# 02_-_Sensor.net
KiCad netlist of a schematic drawn in Altium Designer
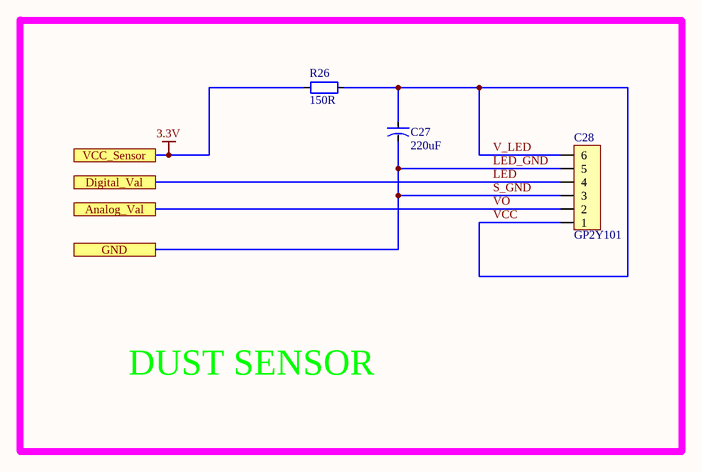
[diagram p0: [02] - Sensor.SchDoc]

(export (version "E")
  (design (tool "Eeschema 10.0.6"))
  (components
    (comp (ref "C27")
      (value "220uF")
      (footprint "CAP-ALU-SMD-D")
      (description "Polarized Capacitor (Axial)")
      (fields (field (name "PUBLISHER") "Altium Limited"))
      (libsource (lib "My Library") (part "CAP-ALU-SMD"))
    )
    (comp (ref "C28")
      (value "GP2Y101")
      (footprint "CON_6P")
      (description "Header IDC, 6 x 1 Pin Vertical 2.54mm Pitch (Non-Boxed, Male)")
      (fields
        (field (name "MANUFACTURER") "Würth Elektronik eiSos GmbH")
        (field (name "PARTNO") "613002143121")
        (field (name "CREATED BY") "Karrer Zheng")
      )
      (libsource (lib "My Library") (part "Header6"))
    )
    (comp (ref "R26")
      (value "150R")
      (footprint "RES-SMD-0603")
      (description "Resistor")
      (fields
        (field (name "MANUFACTURER") "Generic Components")
        (field (name "PUBLISHER") "Altium Hobart Technology Centre")
      )
      (libsource (lib "HS_Lib") (part "Resistor - SMD"))
    )
  )
  (nets
    (net (code "1") (name "/LED") (class "Default")
      (node (ref "C28") (pin "4") (pinfunction "4_4") (pintype "passive"))
    )
    (net (code "2") (name "/LED_GND") (class "Default")
      (node (ref "C27") (pin "2") (pinfunction "2_2") (pintype "passive"))
      (node (ref "C28") (pin "3") (pinfunction "3_3") (pintype "passive"))
      (node (ref "C28") (pin "5") (pinfunction "5_5") (pintype "passive"))
    )
    (net (code "3") (name "/VCC") (class "Default")
      (node (ref "C27") (pin "1") (pinfunction "1_1") (pintype "passive"))
      (node (ref "C28") (pin "1") (pinfunction "1_1") (pintype "passive"))
      (node (ref "C28") (pin "6") (pinfunction "6_6") (pintype "passive"))
      (node (ref "R26") (pin "2") (pinfunction "2_2") (pintype "passive"))
    )
    (net (code "4") (name "/VO") (class "Default")
      (node (ref "C28") (pin "2") (pinfunction "2_2") (pintype "passive"))
    )
    (net (code "5") (name "3.3V") (class "Default")
      (node (ref "R26") (pin "1") (pinfunction "1_1") (pintype "passive"))
    )
  )
)
